# MagnetismCodeDish.net
KiCad netlist of a schematic drawn in Altium Designer
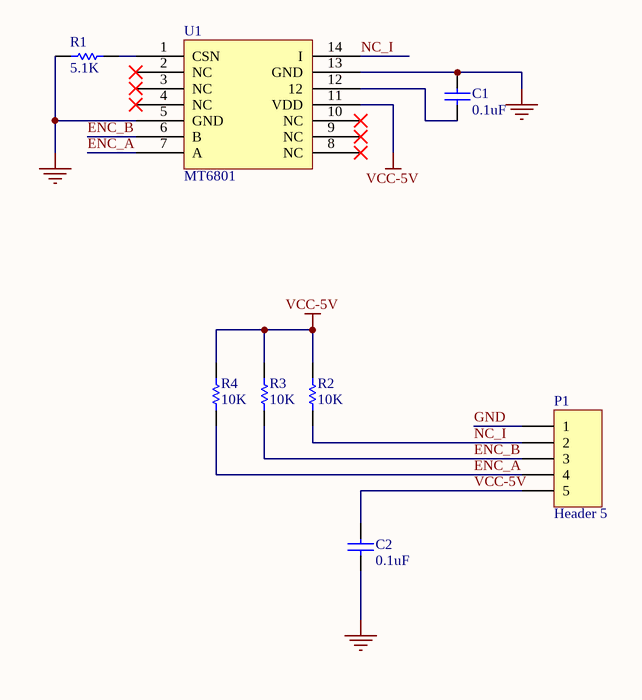
[diagram p0: MagnetismCodeDish.SchDoc]

(export (version "E")
  (design (tool "Eeschema 10.0.6"))
  (components
    (comp (ref "C1")
      (value "0.1uF")
      (footprint "LiyaoPCB库:C0603_M1608")
      (description "电容")
      (fields (field (name "PUBLISHER") "Altium Limited"))
      (libsource (lib "Liyao原理图库") (part "Cap"))
    )
    (comp (ref "C2")
      (value "0.1uF")
      (footprint "C0603_M1608")
      (description "电容")
      (fields (field (name "PUBLISHER") "Altium Limited"))
      (libsource (lib "Liyao原理图库") (part "Cap"))
    )
    (comp (ref "P1")
      (value "Header 5")
      (footprint "PH-AWB-5P")
      (description "Header, 5-Pin")
      (fields (field (name "PUBLISHER") "Altium Limited"))
      (libsource (lib "Miscellaneous Connectors") (part "Header 5"))
    )
    (comp (ref "R1")
      (value "5.1K")
      (footprint "C0603_M1608")
      (description "电阻")
      (fields (field (name "PUBLISHER") "Altium Limited"))
      (libsource (lib "Liyao原理图库") (part "Res"))
    )
    (comp (ref "R2")
      (value "10K")
      (footprint "C0603_M1608")
      (description "电阻")
      (fields (field (name "PUBLISHER") "Altium Limited"))
      (libsource (lib "Liyao原理图库") (part "Res"))
    )
    (comp (ref "R3")
      (value "10K")
      (footprint "C0603_M1608")
      (description "电阻")
      (fields (field (name "PUBLISHER") "Altium Limited"))
      (libsource (lib "Liyao原理图库") (part "Res"))
    )
    (comp (ref "R4")
      (value "10K")
      (footprint "C0603_M1608")
      (description "电阻")
      (fields (field (name "PUBLISHER") "Altium Limited"))
      (libsource (lib "Liyao原理图库") (part "Res"))
    )
    (comp (ref "U1")
      (value "MT6801")
      (footprint "SSOP14_C")
      (description "磁码盘IC")
      (libsource (lib "Liyao原理图库") (part "MT6801"))
    )
  )
  (nets
    (net (code "1") (name "/ENC_A") (class "Default")
      (node (ref "P1") (pin "4") (pinfunction "4_4") (pintype "passive"))
      (node (ref "R4") (pin "1") (pinfunction "1_1") (pintype "passive"))
      (node (ref "U1") (pin "7") (pinfunction "A_7") (pintype "passive"))
    )
    (net (code "2") (name "/ENC_B") (class "Default")
      (node (ref "P1") (pin "3") (pinfunction "3_3") (pintype "passive"))
      (node (ref "R3") (pin "1") (pinfunction "1_1") (pintype "passive"))
      (node (ref "U1") (pin "6") (pinfunction "B_6") (pintype "passive"))
    )
    (net (code "3") (name "/NC_I") (class "Default")
      (node (ref "P1") (pin "2") (pinfunction "2_2") (pintype "passive"))
      (node (ref "R2") (pin "1") (pinfunction "1_1") (pintype "passive"))
      (node (ref "U1") (pin "14") (pinfunction "I_14") (pintype "passive"))
    )
    (net (code "4") (name "GND") (class "Default")
      (node (ref "C1") (pin "2") (pinfunction "2_2") (pintype "passive"))
      (node (ref "C2") (pin "1") (pinfunction "1_1") (pintype "passive"))
      (node (ref "P1") (pin "1") (pinfunction "1_1") (pintype "passive"))
      (node (ref "R1") (pin "2") (pinfunction "2_2") (pintype "passive"))
      (node (ref "U1") (pin "13") (pinfunction "GND_13") (pintype "passive"))
      (node (ref "U1") (pin "5") (pinfunction "GND_5") (pintype "passive"))
    )
    (net (code "5") (name "Net-(C1-Pad1)") (class "Default")
      (node (ref "C1") (pin "1") (pinfunction "1_1") (pintype "passive"))
      (node (ref "U1") (pin "12") (pinfunction "12_12") (pintype "passive"))
    )
    (net (code "6") (name "Net-(U1-CSN)") (class "Default")
      (node (ref "R1") (pin "1") (pinfunction "1_1") (pintype "passive"))
      (node (ref "U1") (pin "1") (pinfunction "CSN_1") (pintype "passive"))
    )
    (net (code "7") (name "VCC-5V") (class "Default")
      (node (ref "C2") (pin "2") (pinfunction "2_2") (pintype "passive"))
      (node (ref "P1") (pin "5") (pinfunction "5_5") (pintype "passive"))
      (node (ref "R2") (pin "2") (pinfunction "2_2") (pintype "passive"))
      (node (ref "R3") (pin "2") (pinfunction "2_2") (pintype "passive"))
      (node (ref "R4") (pin "2") (pinfunction "2_2") (pintype "passive"))
      (node (ref "U1") (pin "11") (pinfunction "VDD_11") (pintype "passive"))
    )
    (net (code "8") (name "unconnected-(U1-NC-Pad2)") (class "Default")
      (node (ref "U1") (pin "2") (pinfunction "NC_2") (pintype "passive+no_connect"))
    )
    (net (code "9") (name "unconnected-(U1-NC-Pad3)") (class "Default")
      (node (ref "U1") (pin "3") (pinfunction "NC_3") (pintype "passive+no_connect"))
    )
    (net (code "10") (name "unconnected-(U1-NC-Pad4)") (class "Default")
      (node (ref "U1") (pin "4") (pinfunction "NC_4") (pintype "passive+no_connect"))
    )
    (net (code "11") (name "unconnected-(U1-NC-Pad8)") (class "Default")
      (node (ref "U1") (pin "8") (pinfunction "NC_8") (pintype "passive+no_connect"))
    )
    (net (code "12") (name "unconnected-(U1-NC-Pad9)") (class "Default")
      (node (ref "U1") (pin "9") (pinfunction "NC_9") (pintype "passive+no_connect"))
    )
    (net (code "13") (name "unconnected-(U1-NC-Pad10)") (class "Default")
      (node (ref "U1") (pin "10") (pinfunction "NC_10") (pintype "passive+no_connect"))
    )
  )
)
